# APU_PayloadBoard_Schematic.net
KiCad netlist of a schematic drawn in EAGLE
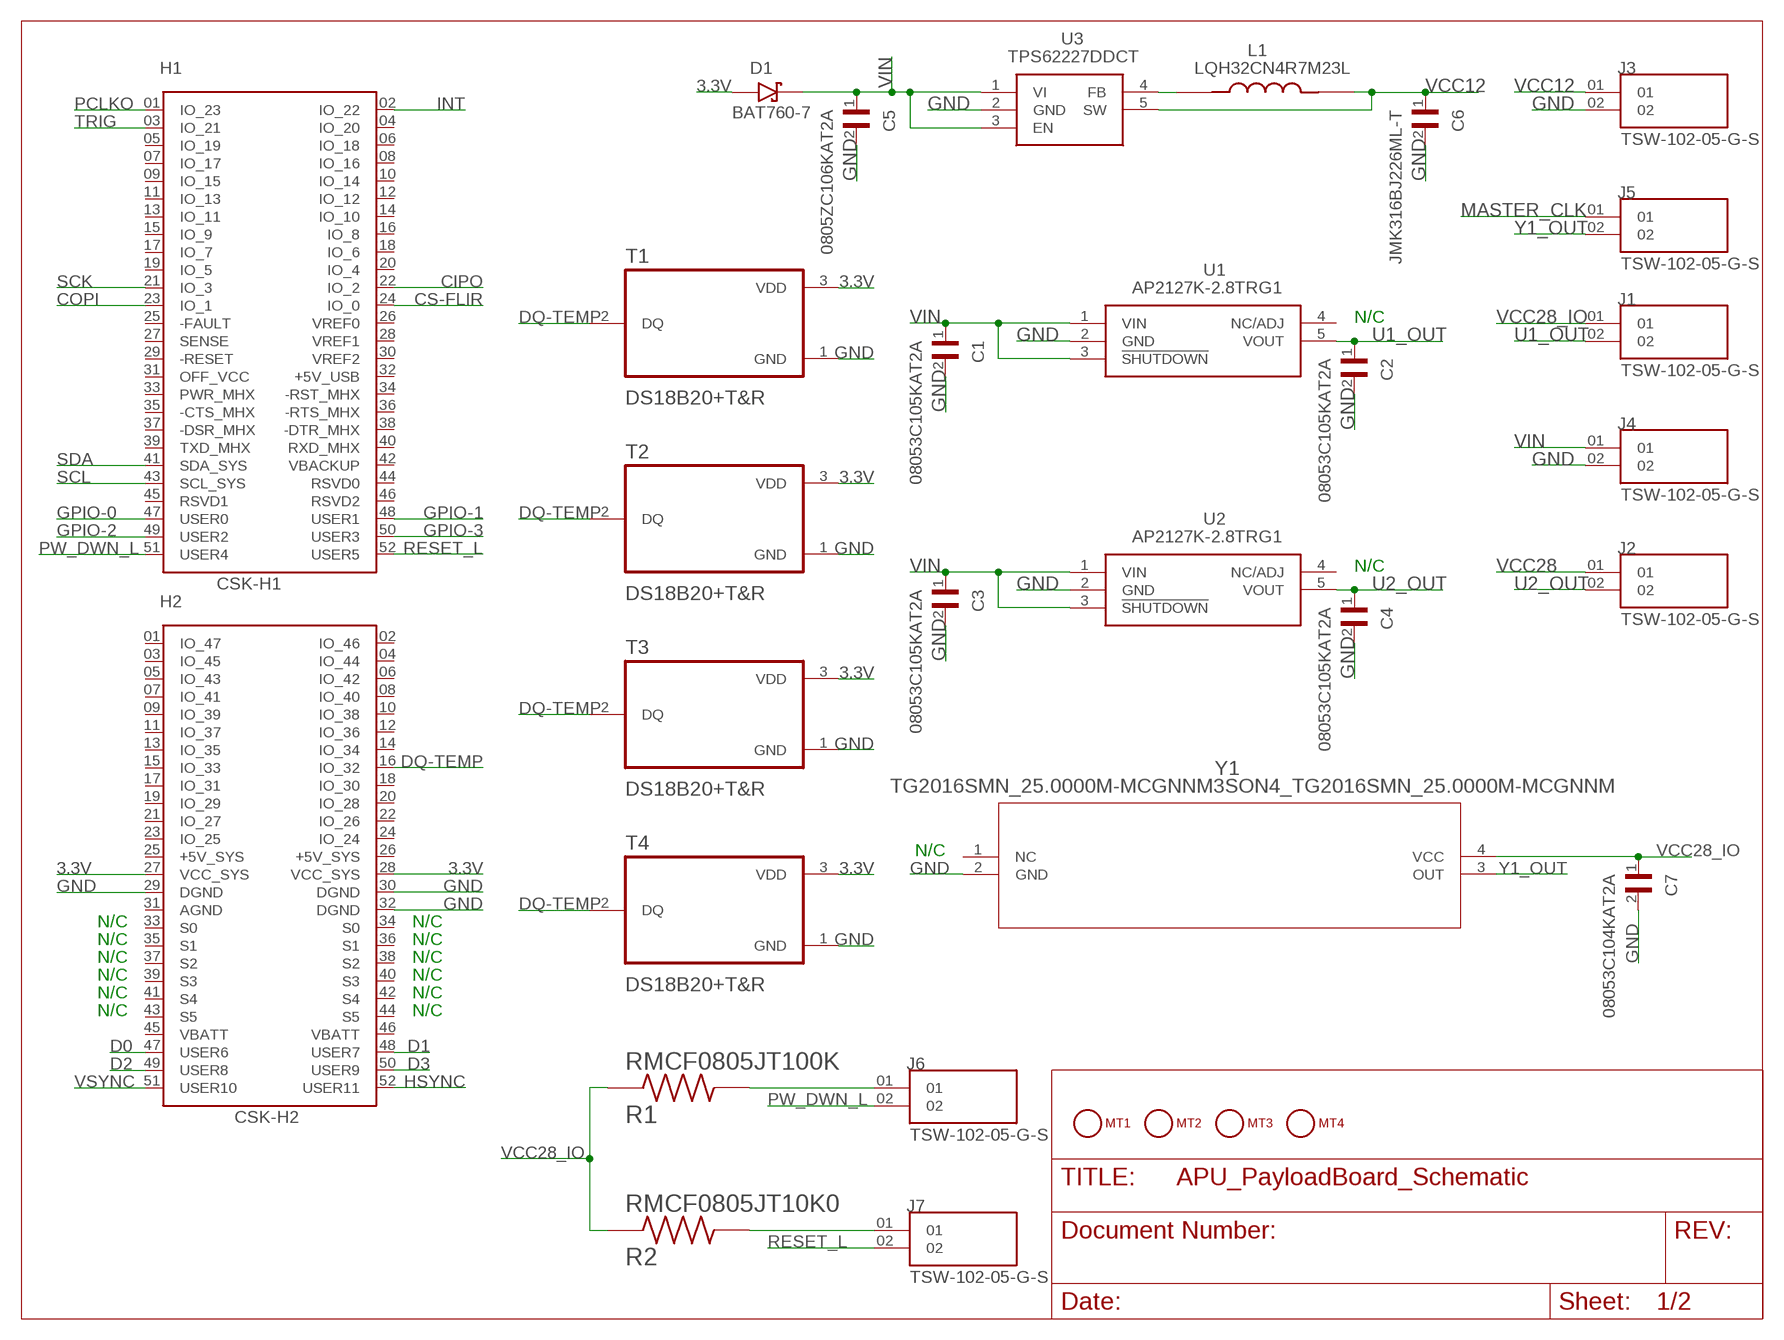
[diagram p0: schematic, sheet 1]
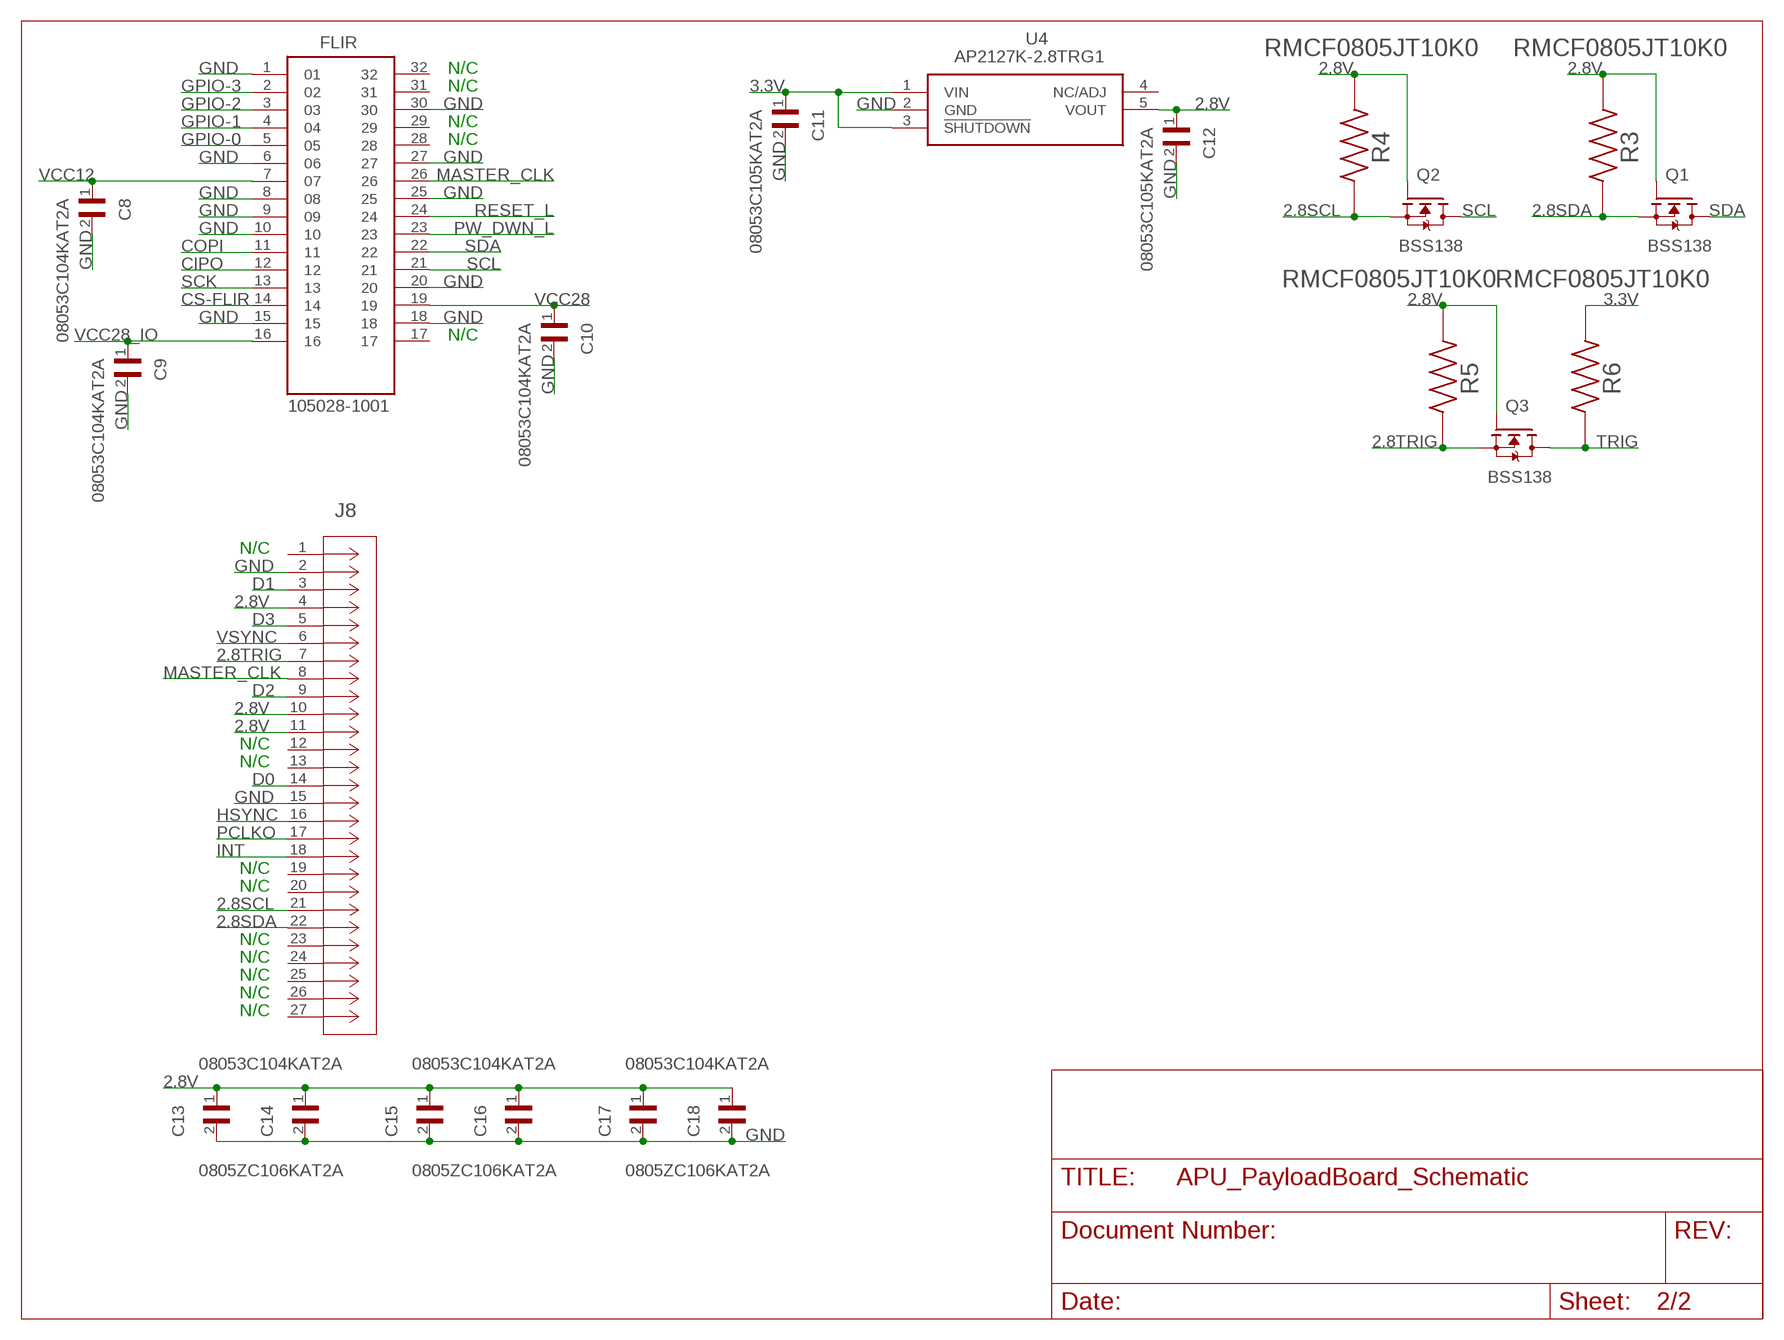
[diagram p1: schematic, sheet 2]

(export (version "E")
  (design (tool "Eeschema 10.0.6"))
  (components
    (comp (ref "C1")
      (value "08053C105KAT2A")
      (footprint "eagle-import:CAPC2012X94N")
      (fields (field (name "MF") "AVX"))
      (libsource (lib "eagle-import") (part "08053C105KAT2A"))
    )
    (comp (ref "C2")
      (value "08053C105KAT2A")
      (footprint "eagle-import:CAPC2012X94N")
      (fields (field (name "MF") "AVX"))
      (libsource (lib "eagle-import") (part "08053C105KAT2A"))
    )
    (comp (ref "C3")
      (value "08053C105KAT2A")
      (footprint "eagle-import:CAPC2012X94N")
      (fields (field (name "MF") "AVX"))
      (libsource (lib "eagle-import") (part "08053C105KAT2A"))
    )
    (comp (ref "C4")
      (value "08053C105KAT2A")
      (footprint "eagle-import:CAPC2012X94N")
      (fields (field (name "MF") "AVX"))
      (libsource (lib "eagle-import") (part "08053C105KAT2A"))
    )
    (comp (ref "C5")
      (value "0805ZC106KAT2A")
      (footprint "eagle-import:CAPC2012X152N")
      (fields (field (name "MF") "AVX"))
      (libsource (lib "eagle-import") (part "0805ZC106KAT2A"))
    )
    (comp (ref "C6")
      (value "JMK316BJ226ML-T")
      (footprint "eagle-import:CAPC3216X180N")
      (fields (field (name "MF") "Taiyo Yuden"))
      (libsource (lib "eagle-import") (part "JMK316BJ226ML-T"))
    )
    (comp (ref "C7")
      (value "08053C104KAT2A")
      (footprint "eagle-import:CAPC2012X94N")
      (fields (field (name "MF") "AVX"))
      (libsource (lib "eagle-import") (part "08053C104KAT2A"))
    )
    (comp (ref "D1")
      (value "BAT760-7")
      (footprint "eagle-import:SOD2513X120N")
      (fields (field (name "MF") "Diodes Inc."))
      (libsource (lib "eagle-import") (part "BAT760-7"))
    )
    (comp (ref "H1")
      (value "CSK-H1")
      (footprint "eagle-import:SAMTEC_ESQ-126-37-G-D--NUMBERED-FOR-CUBESAT-BUS")
      (libsource (lib "eagle-import") (part "CSK-H1"))
    )
    (comp (ref "H2")
      (value "CSK-H2")
      (footprint "eagle-import:SAMTEC_ESQ-126-37-G-D--NUMBERED-FOR-CUBESAT-BUS")
      (libsource (lib "eagle-import") (part "CSK-H2"))
    )
    (comp (ref "J1")
      (value "TSW-102-05-G-S")
      (footprint "eagle-import:SAMTEC_TSW-102-05-G-S")
      (fields (field (name "MF") "Samtec Inc."))
      (libsource (lib "eagle-import") (part "TSW-102-05-G-S"))
    )
    (comp (ref "J2")
      (value "TSW-102-05-G-S")
      (footprint "eagle-import:SAMTEC_TSW-102-05-G-S")
      (fields (field (name "MF") "Samtec Inc."))
      (libsource (lib "eagle-import") (part "TSW-102-05-G-S"))
    )
    (comp (ref "J3")
      (value "TSW-102-05-G-S")
      (footprint "eagle-import:SAMTEC_TSW-102-05-G-S")
      (fields (field (name "MF") "Samtec Inc."))
      (libsource (lib "eagle-import") (part "TSW-102-05-G-S"))
    )
    (comp (ref "J4")
      (value "TSW-102-05-G-S")
      (footprint "eagle-import:SAMTEC_TSW-102-05-G-S")
      (fields (field (name "MF") "Samtec Inc."))
      (libsource (lib "eagle-import") (part "TSW-102-05-G-S"))
    )
    (comp (ref "J5")
      (value "TSW-102-05-G-S")
      (footprint "eagle-import:SAMTEC_TSW-102-05-G-S")
      (fields (field (name "MF") "Samtec Inc."))
      (libsource (lib "eagle-import") (part "TSW-102-05-G-S"))
    )
    (comp (ref "J6")
      (value "TSW-102-05-G-S")
      (footprint "eagle-import:SAMTEC_TSW-102-05-G-S")
      (fields (field (name "MF") "Samtec Inc."))
      (libsource (lib "eagle-import") (part "TSW-102-05-G-S"))
    )
    (comp (ref "J7")
      (value "TSW-102-05-G-S")
      (footprint "eagle-import:SAMTEC_TSW-102-05-G-S")
      (fields (field (name "MF") "Samtec Inc."))
      (libsource (lib "eagle-import") (part "TSW-102-05-G-S"))
    )
    (comp (ref "L1")
      (value "LQH32CN4R7M23L")
      (footprint "eagle-import:IND_LQH32CN4R7M23L")
      (fields (field (name "MF") "Murata Electronics"))
      (libsource (lib "eagle-import") (part "LQH32CN4R7M23L"))
    )
    (comp (ref "MT1")
      (value "MOUNTING_HOLE-125_250_ROUND")
      (footprint "eagle-import:MT_125_250")
      (libsource (lib "eagle-import") (part "MOUNTING_HOLE-125_250_ROUND"))
    )
    (comp (ref "MT2")
      (value "MOUNTING_HOLE-125_250_ROUND")
      (footprint "eagle-import:MT_125_250")
      (libsource (lib "eagle-import") (part "MOUNTING_HOLE-125_250_ROUND"))
    )
    (comp (ref "MT3")
      (value "MOUNTING_HOLE-125_250_ROUND")
      (footprint "eagle-import:MT_125_250")
      (libsource (lib "eagle-import") (part "MOUNTING_HOLE-125_250_ROUND"))
    )
    (comp (ref "MT4")
      (value "MOUNTING_HOLE-125_250_ROUND")
      (footprint "eagle-import:MT_125_250")
      (libsource (lib "eagle-import") (part "MOUNTING_HOLE-125_250_ROUND"))
    )
    (comp (ref "R1")
      (value "RMCF0805JT100K")
      (footprint "eagle-import:RESC2012X65N")
      (fields (field (name "MF") "Stackpole Electronics Inc"))
      (libsource (lib "eagle-import") (part "RMCF0805JT100K"))
    )
    (comp (ref "R2")
      (value "RMCF0805JT10K0")
      (footprint "eagle-import:RESC2012X65N")
      (fields (field (name "MF") "Stackpole Electronics Inc"))
      (libsource (lib "eagle-import") (part "RMCF0805JT10K0"))
    )
    (comp (ref "T1")
      (value "DS18B20+T&R")
      (footprint "eagle-import:DS18B20+T&R")
      (libsource (lib "eagle-import") (part "DS18B20+T&R"))
    )
    (comp (ref "T2")
      (value "DS18B20+T&R")
      (footprint "eagle-import:DS18B20+T&R")
      (libsource (lib "eagle-import") (part "DS18B20+T&R"))
    )
    (comp (ref "T3")
      (value "DS18B20+T&R")
      (footprint "eagle-import:DS18B20+T&R")
      (libsource (lib "eagle-import") (part "DS18B20+T&R"))
    )
    (comp (ref "T4")
      (value "DS18B20+T&R")
      (footprint "eagle-import:DS18B20+T&R")
      (libsource (lib "eagle-import") (part "DS18B20+T&R"))
    )
    (comp (ref "U1")
      (value "AP2127K-2.8TRG1")
      (footprint "eagle-import:SOT95P282X145-5N")
      (fields (field (name "MOUSER_PART_NUMBER") "621-AP2127K-2.8TRG1"))
      (libsource (lib "eagle-import") (part "AP2127K-2.8TRG1"))
    )
    (comp (ref "U2")
      (value "AP2127K-2.8TRG1")
      (footprint "eagle-import:SOT95P282X145-5N")
      (fields (field (name "MOUSER_PART_NUMBER") "621-AP2127K-2.8TRG1"))
      (libsource (lib "eagle-import") (part "AP2127K-2.8TRG1"))
    )
    (comp (ref "U3")
      (value "TPS62227DDCT")
      (footprint "eagle-import:SOT95P280X110-5N")
      (fields (field (name "MOUSER_PART_NUMBER") "595-TPS62227DDCT"))
      (libsource (lib "eagle-import") (part "TPS62227DDCT"))
    )
    (comp (ref "Y1")
      (value "TG2016SMN_25.0000M-MCGNNM3SON4_TG2016SMN_25.0000M-MCGNNM")
      (footprint "eagle-import:SON4_TG2016SMN_25.0000M-MCGNNM")
      (fields
        (field (name "MANUFACTURER_PART_NUMBER") "TG2016SMN 25.0000M-MCGNNM3")
        (field (name "COPYRIGHT") "Copyright (C) 2023 Ultra Librarian. All rights reserved.")
      )
      (libsource (lib "eagle-import") (part "TG2016SMN_25.0000M-MCGNNM3SON4_TG2016SMN_25.0000M-MCGNNM"))
    )
    (comp (ref "C8")
      (value "08053C104KAT2A")
      (footprint "eagle-import:CAPC2012X94N")
      (fields (field (name "MF") "AVX"))
      (libsource (lib "eagle-import") (part "08053C104KAT2A"))
    )
    (comp (ref "C9")
      (value "08053C104KAT2A")
      (footprint "eagle-import:CAPC2012X94N")
      (fields (field (name "MF") "AVX"))
      (libsource (lib "eagle-import") (part "08053C104KAT2A"))
    )
    (comp (ref "C10")
      (value "08053C104KAT2A")
      (footprint "eagle-import:CAPC2012X94N")
      (fields (field (name "MF") "AVX"))
      (libsource (lib "eagle-import") (part "08053C104KAT2A"))
    )
    (comp (ref "C11")
      (value "08053C105KAT2A")
      (footprint "eagle-import:CAPC2012X94N")
      (fields (field (name "MF") "AVX"))
      (libsource (lib "eagle-import") (part "08053C105KAT2A"))
    )
    (comp (ref "C12")
      (value "08053C105KAT2A")
      (footprint "eagle-import:CAPC2012X94N")
      (fields (field (name "MF") "AVX"))
      (libsource (lib "eagle-import") (part "08053C105KAT2A"))
    )
    (comp (ref "C13")
      (value "08053C104KAT2A")
      (footprint "eagle-import:CAPC2012X94N")
      (fields (field (name "MF") "AVX"))
      (libsource (lib "eagle-import") (part "08053C104KAT2A"))
    )
    (comp (ref "C14")
      (value "0805ZC106KAT2A")
      (footprint "eagle-import:CAPC2012X152N")
      (fields (field (name "MF") "AVX"))
      (libsource (lib "eagle-import") (part "0805ZC106KAT2A"))
    )
    (comp (ref "C15")
      (value "08053C104KAT2A")
      (footprint "eagle-import:CAPC2012X94N")
      (fields (field (name "MF") "AVX"))
      (libsource (lib "eagle-import") (part "08053C104KAT2A"))
    )
    (comp (ref "C16")
      (value "0805ZC106KAT2A")
      (footprint "eagle-import:CAPC2012X152N")
      (fields (field (name "MF") "AVX"))
      (libsource (lib "eagle-import") (part "0805ZC106KAT2A"))
    )
    (comp (ref "C17")
      (value "08053C104KAT2A")
      (footprint "eagle-import:CAPC2012X94N")
      (fields (field (name "MF") "AVX"))
      (libsource (lib "eagle-import") (part "08053C104KAT2A"))
    )
    (comp (ref "C18")
      (value "0805ZC106KAT2A")
      (footprint "eagle-import:CAPC2012X152N")
      (fields (field (name "MF") "AVX"))
      (libsource (lib "eagle-import") (part "0805ZC106KAT2A"))
    )
    (comp (ref "FLIR")
      (value "105028-1001")
      (footprint "eagle-import:MOLEX_105028-1001")
      (fields (field (name "MF") "Molex") (field (name "MP") "1050281001"))
      (libsource (lib "eagle-import") (part "105028-1001"))
    )
    (comp (ref "J8")
      (value "SFV25R-1STE1LFCON25_1X25_DR_SFV_JAE")
      (footprint "eagle-import:CON25_1X25_DR_SFV_JAE")
      (fields
        (field (name "MANUFACTURER_PART_NUMBER") "SFV25R-1STE1LF")
        (field (name "COPYRIGHT") "Copyright (C) 2023 Ultra Librarian. All rights reserved.")
      )
      (libsource (lib "eagle-import") (part "SFV25R-1STE1LFCON25_1X25_DR_SFV_JAE"))
    )
    (comp (ref "Q1")
      (value "BSS138")
      (footprint "eagle-import:SOT95P240X111-3N")
      (fields (field (name "MF") "onsemi"))
      (libsource (lib "eagle-import") (part "BSS138"))
    )
    (comp (ref "Q2")
      (value "BSS138")
      (footprint "eagle-import:SOT95P240X111-3N")
      (fields (field (name "MF") "onsemi"))
      (libsource (lib "eagle-import") (part "BSS138"))
    )
    (comp (ref "Q3")
      (value "BSS138")
      (footprint "eagle-import:SOT95P240X111-3N")
      (fields (field (name "MF") "onsemi"))
      (libsource (lib "eagle-import") (part "BSS138"))
    )
    (comp (ref "R3")
      (value "RMCF0805JT10K0")
      (footprint "eagle-import:RESC2012X65N")
      (fields (field (name "MF") "Stackpole Electronics Inc"))
      (libsource (lib "eagle-import") (part "RMCF0805JT10K0"))
    )
    (comp (ref "R4")
      (value "RMCF0805JT10K0")
      (footprint "eagle-import:RESC2012X65N")
      (fields (field (name "MF") "Stackpole Electronics Inc"))
      (libsource (lib "eagle-import") (part "RMCF0805JT10K0"))
    )
    (comp (ref "R5")
      (value "RMCF0805JT10K0")
      (footprint "eagle-import:RESC2012X65N")
      (fields (field (name "MF") "Stackpole Electronics Inc"))
      (libsource (lib "eagle-import") (part "RMCF0805JT10K0"))
    )
    (comp (ref "R6")
      (value "RMCF0805JT10K0")
      (footprint "eagle-import:RESC2012X65N")
      (fields (field (name "MF") "Stackpole Electronics Inc"))
      (libsource (lib "eagle-import") (part "RMCF0805JT10K0"))
    )
    (comp (ref "U4")
      (value "AP2127K-2.8TRG1")
      (footprint "eagle-import:SOT95P282X145-5N")
      (fields (field (name "MOUSER_PART_NUMBER") "621-AP2127K-2.8TRG1"))
      (libsource (lib "eagle-import") (part "AP2127K-2.8TRG1"))
    )
  )
  (nets
    (net (code "1") (name "2.8SCL") (class "Default")
      (node (ref "J8") (pin "21") (pinfunction "21_21") (pintype "passive"))
      (node (ref "Q2") (pin "2") (pinfunction "S_2") (pintype "passive"))
      (node (ref "R4") (pin "1") (pinfunction "1_1") (pintype "passive"))
    )
    (net (code "2") (name "2.8SDA") (class "Default")
      (node (ref "J8") (pin "22") (pinfunction "22_22") (pintype "passive"))
      (node (ref "Q1") (pin "2") (pinfunction "S_2") (pintype "passive"))
      (node (ref "R3") (pin "1") (pinfunction "1_1") (pintype "passive"))
    )
    (net (code "3") (name "2.8TRIG") (class "Default")
      (node (ref "J8") (pin "7") (pinfunction "7_7") (pintype "passive"))
      (node (ref "Q3") (pin "2") (pinfunction "S_2") (pintype "passive"))
      (node (ref "R5") (pin "1") (pinfunction "1_1") (pintype "passive"))
    )
    (net (code "4") (name "2.8V") (class "Default")
      (node (ref "C12") (pin "1") (pinfunction "1_1") (pintype "passive"))
      (node (ref "C13") (pin "1") (pinfunction "1_1") (pintype "passive"))
      (node (ref "C14") (pin "1") (pinfunction "1_1") (pintype "passive"))
      (node (ref "C15") (pin "1") (pinfunction "1_1") (pintype "passive"))
      (node (ref "C16") (pin "1") (pinfunction "1_1") (pintype "passive"))
      (node (ref "C17") (pin "1") (pinfunction "1_1") (pintype "passive"))
      (node (ref "C18") (pin "1") (pinfunction "1_1") (pintype "passive"))
      (node (ref "J8") (pin "10") (pinfunction "10_10") (pintype "passive"))
      (node (ref "J8") (pin "11") (pinfunction "11_11") (pintype "passive"))
      (node (ref "J8") (pin "4") (pinfunction "4_4") (pintype "passive"))
      (node (ref "Q1") (pin "1") (pinfunction "G_1") (pintype "passive"))
      (node (ref "Q2") (pin "1") (pinfunction "G_1") (pintype "passive"))
      (node (ref "Q3") (pin "1") (pinfunction "G_1") (pintype "passive"))
      (node (ref "R3") (pin "2") (pinfunction "2_2") (pintype "passive"))
      (node (ref "R4") (pin "2") (pinfunction "2_2") (pintype "passive"))
      (node (ref "R5") (pin "2") (pinfunction "2_2") (pintype "passive"))
      (node (ref "U4") (pin "5") (pinfunction "VOUT_5") (pintype "bidirectional"))
    )
    (net (code "5") (name "3.3V") (class "Default")
      (node (ref "C11") (pin "1") (pinfunction "1_1") (pintype "passive"))
      (node (ref "D1") (pin "A") (pinfunction "A_A") (pintype "passive"))
      (node (ref "H2") (pin "27") (pinfunction "VCC_SYS_27") (pintype "bidirectional"))
      (node (ref "H2") (pin "28") (pinfunction "VCC_SYS_28") (pintype "bidirectional"))
      (node (ref "R6") (pin "2") (pinfunction "2_2") (pintype "passive"))
      (node (ref "T1") (pin "3") (pinfunction "VDD_3") (pintype "bidirectional"))
      (node (ref "T2") (pin "3") (pinfunction "VDD_3") (pintype "bidirectional"))
      (node (ref "T3") (pin "3") (pinfunction "VDD_3") (pintype "bidirectional"))
      (node (ref "T4") (pin "3") (pinfunction "VDD_3") (pintype "bidirectional"))
      (node (ref "U4") (pin "1") (pinfunction "VIN_1") (pintype "bidirectional"))
      (node (ref "U4") (pin "3") (pinfunction "~{SHUTDOWN}_3") (pintype "bidirectional"))
    )
    (net (code "6") (name "CIPO") (class "Default")
      (node (ref "FLIR") (pin "12") (pinfunction "12_12") (pintype "passive"))
      (node (ref "H1") (pin "22") (pinfunction "IO_2_22") (pintype "bidirectional"))
    )
    (net (code "7") (name "COPI") (class "Default")
      (node (ref "FLIR") (pin "11") (pinfunction "11_11") (pintype "passive"))
      (node (ref "H1") (pin "23") (pinfunction "IO_1_23") (pintype "bidirectional"))
    )
    (net (code "8") (name "CS-FLIR") (class "Default")
      (node (ref "FLIR") (pin "14") (pinfunction "14_14") (pintype "passive"))
      (node (ref "H1") (pin "24") (pinfunction "IO_0_24") (pintype "bidirectional"))
    )
    (net (code "9") (name "D0") (class "Default")
      (node (ref "H2") (pin "47") (pinfunction "USER6_47") (pintype "bidirectional"))
      (node (ref "J8") (pin "14") (pinfunction "14_14") (pintype "passive"))
    )
    (net (code "10") (name "D1") (class "Default")
      (node (ref "H2") (pin "48") (pinfunction "USER7_48") (pintype "bidirectional"))
      (node (ref "J8") (pin "3") (pinfunction "3_3") (pintype "passive"))
    )
    (net (code "11") (name "D2") (class "Default")
      (node (ref "H2") (pin "49") (pinfunction "USER8_49") (pintype "bidirectional"))
      (node (ref "J8") (pin "9") (pinfunction "9_9") (pintype "passive"))
    )
    (net (code "12") (name "D3") (class "Default")
      (node (ref "H2") (pin "50") (pinfunction "USER9_50") (pintype "bidirectional"))
      (node (ref "J8") (pin "5") (pinfunction "5_5") (pintype "passive"))
    )
    (net (code "13") (name "DQ-TEMP") (class "Default")
      (node (ref "H2") (pin "16") (pinfunction "IO_32_16") (pintype "bidirectional"))
      (node (ref "T1") (pin "2") (pinfunction "DQ_2") (pintype "bidirectional"))
      (node (ref "T2") (pin "2") (pinfunction "DQ_2") (pintype "bidirectional"))
      (node (ref "T3") (pin "2") (pinfunction "DQ_2") (pintype "bidirectional"))
      (node (ref "T4") (pin "2") (pinfunction "DQ_2") (pintype "bidirectional"))
    )
    (net (code "14") (name "GND") (class "Default")
      (node (ref "C1") (pin "2") (pinfunction "2_2") (pintype "passive"))
      (node (ref "C10") (pin "2") (pinfunction "2_2") (pintype "passive"))
      (node (ref "C11") (pin "2") (pinfunction "2_2") (pintype "passive"))
      (node (ref "C12") (pin "2") (pinfunction "2_2") (pintype "passive"))
      (node (ref "C13") (pin "2") (pinfunction "2_2") (pintype "passive"))
      (node (ref "C14") (pin "2") (pinfunction "2_2") (pintype "passive"))
      (node (ref "C15") (pin "2") (pinfunction "2_2") (pintype "passive"))
      (node (ref "C16") (pin "2") (pinfunction "2_2") (pintype "passive"))
      (node (ref "C17") (pin "2") (pinfunction "2_2") (pintype "passive"))
      (node (ref "C18") (pin "2") (pinfunction "2_2") (pintype "passive"))
      (node (ref "C2") (pin "2") (pinfunction "2_2") (pintype "passive"))
      (node (ref "C3") (pin "2") (pinfunction "2_2") (pintype "passive"))
      (node (ref "C4") (pin "2") (pinfunction "2_2") (pintype "passive"))
      (node (ref "C5") (pin "2") (pinfunction "2_2") (pintype "passive"))
      (node (ref "C6") (pin "2") (pinfunction "2_2") (pintype "passive"))
      (node (ref "C7") (pin "2") (pinfunction "2_2") (pintype "passive"))
      (node (ref "C8") (pin "2") (pinfunction "2_2") (pintype "passive"))
      (node (ref "C9") (pin "2") (pinfunction "2_2") (pintype "passive"))
      (node (ref "FLIR") (pin "1") (pinfunction "01_1") (pintype "passive"))
      (node (ref "FLIR") (pin "10") (pinfunction "10_10") (pintype "passive"))
      (node (ref "FLIR") (pin "15") (pinfunction "15_15") (pintype "passive"))
      (node (ref "FLIR") (pin "18") (pinfunction "18_18") (pintype "passive"))
      (node (ref "FLIR") (pin "20") (pinfunction "20_20") (pintype "passive"))
      (node (ref "FLIR") (pin "25") (pinfunction "25_25") (pintype "passive"))
      (node (ref "FLIR") (pin "27") (pinfunction "27_27") (pintype "passive"))
      (node (ref "FLIR") (pin "30") (pinfunction "30_30") (pintype "passive"))
      (node (ref "FLIR") (pin "6") (pinfunction "06_6") (pintype "passive"))
      (node (ref "FLIR") (pin "8") (pinfunction "08_8") (pintype "passive"))
      (node (ref "FLIR") (pin "9") (pinfunction "09_9") (pintype "passive"))
      (node (ref "H2") (pin "29") (pinfunction "DGND_29") (pintype "bidirectional"))
      (node (ref "H2") (pin "30") (pinfunction "DGND_30") (pintype "bidirectional"))
      (node (ref "H2") (pin "32") (pinfunction "DGND_32") (pintype "bidirectional"))
      (node (ref "J3") (pin "02") (pinfunction "02_02") (pintype "passive"))
      (node (ref "J4") (pin "02") (pinfunction "02_02") (pintype "passive"))
      (node (ref "J8") (pin "15") (pinfunction "15_15") (pintype "passive"))
      (node (ref "J8") (pin "2") (pinfunction "2_2") (pintype "passive"))
      (node (ref "T1") (pin "1") (pinfunction "GND_1") (pintype "bidirectional"))
      (node (ref "T2") (pin "1") (pinfunction "GND_1") (pintype "bidirectional"))
      (node (ref "T3") (pin "1") (pinfunction "GND_1") (pintype "bidirectional"))
      (node (ref "T4") (pin "1") (pinfunction "GND_1") (pintype "bidirectional"))
      (node (ref "U1") (pin "2") (pinfunction "GND_2") (pintype "bidirectional"))
      (node (ref "U2") (pin "2") (pinfunction "GND_2") (pintype "bidirectional"))
      (node (ref "U3") (pin "2") (pinfunction "GND_2") (pintype "bidirectional"))
      (node (ref "U4") (pin "2") (pinfunction "GND_2") (pintype "bidirectional"))
      (node (ref "Y1") (pin "2") (pinfunction "GND_2") (pintype "passive"))
    )
    (net (code "15") (name "GPIO-0") (class "Default")
      (node (ref "FLIR") (pin "5") (pinfunction "05_5") (pintype "passive"))
      (node (ref "H1") (pin "47") (pinfunction "USER0_47") (pintype "bidirectional"))
    )
    (net (code "16") (name "GPIO-1") (class "Default")
      (node (ref "FLIR") (pin "4") (pinfunction "04_4") (pintype "passive"))
      (node (ref "H1") (pin "48") (pinfunction "USER1_48") (pintype "bidirectional"))
    )
    (net (code "17") (name "GPIO-2") (class "Default")
      (node (ref "FLIR") (pin "3") (pinfunction "03_3") (pintype "passive"))
      (node (ref "H1") (pin "49") (pinfunction "USER2_49") (pintype "bidirectional"))
    )
    (net (code "18") (name "GPIO-3") (class "Default")
      (node (ref "FLIR") (pin "2") (pinfunction "02_2") (pintype "passive"))
      (node (ref "H1") (pin "50") (pinfunction "USER3_50") (pintype "bidirectional"))
    )
    (net (code "19") (name "HSYNC") (class "Default")
      (node (ref "H2") (pin "52") (pinfunction "USER11_52") (pintype "bidirectional"))
      (node (ref "J8") (pin "16") (pinfunction "16_16") (pintype "passive"))
    )
    (net (code "20") (name "INT") (class "Default")
      (node (ref "H1") (pin "02") (pinfunction "IO_22_02") (pintype "bidirectional"))
      (node (ref "J8") (pin "18") (pinfunction "18_18") (pintype "passive"))
    )
    (net (code "21") (name "MASTER_CLK") (class "Default")
      (node (ref "FLIR") (pin "26") (pinfunction "26_26") (pintype "passive"))
      (node (ref "J5") (pin "01") (pinfunction "01_01") (pintype "passive"))
      (node (ref "J8") (pin "8") (pinfunction "8_8") (pintype "passive"))
    )
    (net (code "22") (name "Net-(J6-Pad01)") (class "Default")
      (node (ref "J6") (pin "01") (pinfunction "01_01") (pintype "passive"))
      (node (ref "R1") (pin "2") (pinfunction "2_2") (pintype "passive"))
    )
    (net (code "23") (name "Net-(J7-Pad01)") (class "Default")
      (node (ref "J7") (pin "01") (pinfunction "01_01") (pintype "passive"))
      (node (ref "R2") (pin "2") (pinfunction "2_2") (pintype "passive"))
    )
    (net (code "24") (name "Net-(U3-FB)") (class "Default")
      (node (ref "L1") (pin "1") (pinfunction "1_1") (pintype "passive"))
      (node (ref "U3") (pin "4") (pinfunction "FB_4") (pintype "bidirectional"))
    )
    (net (code "25") (name "PCLKO") (class "Default")
      (node (ref "H1") (pin "01") (pinfunction "IO_23_01") (pintype "bidirectional"))
      (node (ref "J8") (pin "17") (pinfunction "17_17") (pintype "passive"))
    )
    (net (code "26") (name "PW_DWN_L") (class "Default")
      (node (ref "FLIR") (pin "23") (pinfunction "23_23") (pintype "passive"))
      (node (ref "H1") (pin "51") (pinfunction "USER4_51") (pintype "bidirectional"))
      (node (ref "J6") (pin "02") (pinfunction "02_02") (pintype "passive"))
    )
    (net (code "27") (name "RESET_L") (class "Default")
      (node (ref "FLIR") (pin "24") (pinfunction "24_24") (pintype "passive"))
      (node (ref "H1") (pin "52") (pinfunction "USER5_52") (pintype "bidirectional"))
      (node (ref "J7") (pin "02") (pinfunction "02_02") (pintype "passive"))
    )
    (net (code "28") (name "SCK") (class "Default")
      (node (ref "FLIR") (pin "13") (pinfunction "13_13") (pintype "passive"))
      (node (ref "H1") (pin "21") (pinfunction "IO_3_21") (pintype "bidirectional"))
    )
    (net (code "29") (name "SCL") (class "Default")
      (node (ref "FLIR") (pin "21") (pinfunction "21_21") (pintype "passive"))
      (node (ref "H1") (pin "43") (pinfunction "SCL_SYS_43") (pintype "bidirectional"))
      (node (ref "Q2") (pin "3") (pinfunction "D_3") (pintype "passive"))
    )
    (net (code "30") (name "SDA") (class "Default")
      (node (ref "FLIR") (pin "22") (pinfunction "22_22") (pintype "passive"))
      (node (ref "H1") (pin "41") (pinfunction "SDA_SYS_41") (pintype "bidirectional"))
      (node (ref "Q1") (pin "3") (pinfunction "D_3") (pintype "passive"))
    )
    (net (code "31") (name "TRIG") (class "Default")
      (node (ref "H1") (pin "03") (pinfunction "IO_21_03") (pintype "bidirectional"))
      (node (ref "Q3") (pin "3") (pinfunction "D_3") (pintype "passive"))
      (node (ref "R6") (pin "1") (pinfunction "1_1") (pintype "passive"))
    )
    (net (code "32") (name "U1_OUT") (class "Default")
      (node (ref "C2") (pin "1") (pinfunction "1_1") (pintype "passive"))
      (node (ref "J1") (pin "02") (pinfunction "02_02") (pintype "passive"))
      (node (ref "U1") (pin "5") (pinfunction "VOUT_5") (pintype "bidirectional"))
    )
    (net (code "33") (name "U2_OUT") (class "Default")
      (node (ref "C4") (pin "1") (pinfunction "1_1") (pintype "passive"))
      (node (ref "J2") (pin "02") (pinfunction "02_02") (pintype "passive"))
      (node (ref "U2") (pin "5") (pinfunction "VOUT_5") (pintype "bidirectional"))
    )
    (net (code "34") (name "VCC12") (class "Default")
      (node (ref "C6") (pin "1") (pinfunction "1_1") (pintype "passive"))
      (node (ref "C8") (pin "1") (pinfunction "1_1") (pintype "passive"))
      (node (ref "FLIR") (pin "7") (pinfunction "07_7") (pintype "passive"))
      (node (ref "J3") (pin "01") (pinfunction "01_01") (pintype "passive"))
      (node (ref "L1") (pin "2") (pinfunction "2_2") (pintype "passive"))
      (node (ref "U3") (pin "5") (pinfunction "SW_5") (pintype "bidirectional"))
    )
    (net (code "35") (name "VCC28") (class "Default")
      (node (ref "C10") (pin "1") (pinfunction "1_1") (pintype "passive"))
      (node (ref "FLIR") (pin "19") (pinfunction "19_19") (pintype "passive"))
      (node (ref "J2") (pin "01") (pinfunction "01_01") (pintype "passive"))
    )
    (net (code "36") (name "VCC28_IO") (class "Default")
      (node (ref "C7") (pin "1") (pinfunction "1_1") (pintype "passive"))
      (node (ref "C9") (pin "1") (pinfunction "1_1") (pintype "passive"))
      (node (ref "FLIR") (pin "16") (pinfunction "16_16") (pintype "passive"))
      (node (ref "J1") (pin "01") (pinfunction "01_01") (pintype "passive"))
      (node (ref "R1") (pin "1") (pinfunction "1_1") (pintype "passive"))
      (node (ref "R2") (pin "1") (pinfunction "1_1") (pintype "passive"))
      (node (ref "Y1") (pin "4") (pinfunction "VCC_4") (pintype "power_in"))
    )
    (net (code "37") (name "VIN") (class "Default")
      (node (ref "C1") (pin "1") (pinfunction "1_1") (pintype "passive"))
      (node (ref "C3") (pin "1") (pinfunction "1_1") (pintype "passive"))
      (node (ref "C5") (pin "1") (pinfunction "1_1") (pintype "passive"))
      (node (ref "D1") (pin "C") (pinfunction "K_C") (pintype "passive"))
      (node (ref "J4") (pin "01") (pinfunction "01_01") (pintype "passive"))
      (node (ref "U1") (pin "1") (pinfunction "VIN_1") (pintype "bidirectional"))
      (node (ref "U1") (pin "3") (pinfunction "~{SHUTDOWN}_3") (pintype "bidirectional"))
      (node (ref "U2") (pin "1") (pinfunction "VIN_1") (pintype "bidirectional"))
      (node (ref "U2") (pin "3") (pinfunction "~{SHUTDOWN}_3") (pintype "bidirectional"))
      (node (ref "U3") (pin "1") (pinfunction "VI_1") (pintype "bidirectional"))
      (node (ref "U3") (pin "3") (pinfunction "EN_3") (pintype "bidirectional"))
    )
    (net (code "38") (name "VSYNC") (class "Default")
      (node (ref "H2") (pin "51") (pinfunction "USER10_51") (pintype "bidirectional"))
      (node (ref "J8") (pin "6") (pinfunction "6_6") (pintype "passive"))
    )
    (net (code "39") (name "Y1_OUT") (class "Default")
      (node (ref "J5") (pin "02") (pinfunction "02_02") (pintype "passive"))
      (node (ref "Y1") (pin "3") (pinfunction "OUT_3") (pintype "output"))
    )
    (net (code "40") (name "unconnected-(FLIR-Pad17)") (class "Default")
      (node (ref "FLIR") (pin "17") (pinfunction "17_17") (pintype "passive"))
    )
    (net (code "41") (name "unconnected-(FLIR-Pad28)") (class "Default")
      (node (ref "FLIR") (pin "28") (pinfunction "28_28") (pintype "passive"))
    )
    (net (code "42") (name "unconnected-(FLIR-Pad29)") (class "Default")
      (node (ref "FLIR") (pin "29") (pinfunction "29_29") (pintype "passive"))
    )
    (net (code "43") (name "unconnected-(FLIR-Pad31)") (class "Default")
      (node (ref "FLIR") (pin "31") (pinfunction "31_31") (pintype "passive"))
    )
    (net (code "44") (name "unconnected-(FLIR-Pad32)") (class "Default")
      (node (ref "FLIR") (pin "32") (pinfunction "32_32") (pintype "passive"))
    )
    (net (code "45") (name "unconnected-(H1-+5V_USB-Pad32)") (class "Default")
      (node (ref "H1") (pin "32") (pinfunction "+5V_USB_32") (pintype "bidirectional"))
    )
    (net (code "46") (name "unconnected-(H1--CTS_MHX-Pad35)") (class "Default")
      (node (ref "H1") (pin "35") (pinfunction "-CTS_MHX_35") (pintype "bidirectional"))
    )
    (net (code "47") (name "unconnected-(H1--DSR_MHX-Pad37)") (class "Default")
      (node (ref "H1") (pin "37") (pinfunction "-DSR_MHX_37") (pintype "bidirectional"))
    )
    (net (code "48") (name "unconnected-(H1--DTR_MHX-Pad38)") (class "Default")
      (node (ref "H1") (pin "38") (pinfunction "-DTR_MHX_38") (pintype "bidirectional"))
    )
    (net (code "49") (name "unconnected-(H1--FAULT-Pad25)") (class "Default")
      (node (ref "H1") (pin "25") (pinfunction "-FAULT_25") (pintype "bidirectional"))
    )
    (net (code "50") (name "unconnected-(H1--RESET-Pad29)") (class "Default")
      (node (ref "H1") (pin "29") (pinfunction "-RESET_29") (pintype "bidirectional"))
    )
    (net (code "51") (name "unconnected-(H1--RST_MHX-Pad34)") (class "Default")
      (node (ref "H1") (pin "34") (pinfunction "-RST_MHX_34") (pintype "bidirectional"))
    )
    (net (code "52") (name "unconnected-(H1--RTS_MHX-Pad36)") (class "Default")
      (node (ref "H1") (pin "36") (pinfunction "-RTS_MHX_36") (pintype "bidirectional"))
    )
    (net (code "53") (name "unconnected-(H1-IO_4-Pad20)") (class "Default")
      (node (ref "H1") (pin "20") (pinfunction "IO_4_20") (pintype "bidirectional"))
    )
    (net (code "54") (name "unconnected-(H1-IO_5-Pad19)") (class "Default")
      (node (ref "H1") (pin "19") (pinfunction "IO_5_19") (pintype "bidirectional"))
    )
    (net (code "55") (name "unconnected-(H1-IO_6-Pad18)") (class "Default")
      (node (ref "H1") (pin "18") (pinfunction "IO_6_18") (pintype "bidirectional"))
    )
    (net (code "56") (name "unconnected-(H1-IO_7-Pad17)") (class "Default")
      (node (ref "H1") (pin "17") (pinfunction "IO_7_17") (pintype "bidirectional"))
    )
    (net (code "57") (name "unconnected-(H1-IO_8-Pad16)") (class "Default")
      (node (ref "H1") (pin "16") (pinfunction "IO_8_16") (pintype "bidirectional"))
    )
    (net (code "58") (name "unconnected-(H1-IO_9-Pad15)") (class "Default")
      (node (ref "H1") (pin "15") (pinfunction "IO_9_15") (pintype "bidirectional"))
    )
    (net (code "59") (name "unconnected-(H1-IO_10-Pad14)") (class "Default")
      (node (ref "H1") (pin "14") (pinfunction "IO_10_14") (pintype "bidirectional"))
    )
    (net (code "60") (name "unconnected-(H1-IO_11-Pad13)") (class "Default")
      (node (ref "H1") (pin "13") (pinfunction "IO_11_13") (pintype "bidirectional"))
    )
    (net (code "61") (name "unconnected-(H1-IO_12-Pad12)") (class "Default")
      (node (ref "H1") (pin "12") (pinfunction "IO_12_12") (pintype "bidirectional"))
    )
    (net (code "62") (name "unconnected-(H1-IO_13-Pad11)") (class "Default")
      (node (ref "H1") (pin "11") (pinfunction "IO_13_11") (pintype "bidirectional"))
    )
    (net (code "63") (name "unconnected-(H1-IO_14-Pad10)") (class "Default")
      (node (ref "H1") (pin "10") (pinfunction "IO_14_10") (pintype "bidirectional"))
    )
    (net (code "64") (name "unconnected-(H1-IO_15-Pad09)") (class "Default")
      (node (ref "H1") (pin "09") (pinfunction "IO_15_09") (pintype "bidirectional"))
    )
    (net (code "65") (name "unconnected-(H1-IO_16-Pad08)") (class "Default")
      (node (ref "H1") (pin "08") (pinfunction "IO_16_08") (pintype "bidirectional"))
    )
    (net (code "66") (name "unconnected-(H1-IO_17-Pad07)") (class "Default")
      (node (ref "H1") (pin "07") (pinfunction "IO_17_07") (pintype "bidirectional"))
    )
    (net (code "67") (name "unconnected-(H1-IO_18-Pad06)") (class "Default")
      (node (ref "H1") (pin "06") (pinfunction "IO_18_06") (pintype "bidirectional"))
    )
    (net (code "68") (name "unconnected-(H1-IO_19-Pad05)") (class "Default")
      (node (ref "H1") (pin "05") (pinfunction "IO_19_05") (pintype "bidirectional"))
    )
    (net (code "69") (name "unconnected-(H1-IO_20-Pad04)") (class "Default")
      (node (ref "H1") (pin "04") (pinfunction "IO_20_04") (pintype "bidirectional"))
    )
    (net (code "70") (name "unconnected-(H1-OFF_VCC-Pad31)") (class "Default")
      (node (ref "H1") (pin "31") (pinfunction "OFF_VCC_31") (pintype "bidirectional"))
    )
    (net (code "71") (name "unconnected-(H1-PWR_MHX-Pad33)") (class "Default")
      (node (ref "H1") (pin "33") (pinfunction "PWR_MHX_33") (pintype "bidirectional"))
    )
    (net (code "72") (name "unconnected-(H1-RSVD0-Pad44)") (class "Default")
      (node (ref "H1") (pin "44") (pinfunction "RSVD0_44") (pintype "bidirectional"))
    )
    (net (code "73") (name "unconnected-(H1-RSVD1-Pad45)") (class "Default")
      (node (ref "H1") (pin "45") (pinfunction "RSVD1_45") (pintype "bidirectional"))
    )
    (net (code "74") (name "unconnected-(H1-RSVD2-Pad46)") (class "Default")
      (node (ref "H1") (pin "46") (pinfunction "RSVD2_46") (pintype "bidirectional"))
    )
    (net (code "75") (name "unconnected-(H1-RXD_MHX-Pad40)") (class "Default")
      (node (ref "H1") (pin "40") (pinfunction "RXD_MHX_40") (pintype "bidirectional"))
    )
    (net (code "76") (name "unconnected-(H1-SENSE-Pad27)") (class "Default")
      (node (ref "H1") (pin "27") (pinfunction "SENSE_27") (pintype "bidirectional"))
    )
    (net (code "77") (name "unconnected-(H1-TXD_MHX-Pad39)") (class "Default")
      (node (ref "H1") (pin "39") (pinfunction "TXD_MHX_39") (pintype "bidirectional"))
    )
    (net (code "78") (name "unconnected-(H1-VBACKUP-Pad42)") (class "Default")
      (node (ref "H1") (pin "42") (pinfunction "VBACKUP_42") (pintype "bidirectional"))
    )
    (net (code "79") (name "unconnected-(H1-VREF0-Pad26)") (class "Default")
      (node (ref "H1") (pin "26") (pinfunction "VREF0_26") (pintype "bidirectional"))
    )
    (net (code "80") (name "unconnected-(H1-VREF1-Pad28)") (class "Default")
      (node (ref "H1") (pin "28") (pinfunction "VREF1_28") (pintype "bidirectional"))
    )
    (net (code "81") (name "unconnected-(H1-VREF2-Pad30)") (class "Default")
      (node (ref "H1") (pin "30") (pinfunction "VREF2_30") (pintype "bidirectional"))
    )
    (net (code "82") (name "unconnected-(H2-+5V_SYS-Pad25)") (class "Default")
      (node (ref "H2") (pin "25") (pinfunction "+5V_SYS_25") (pintype "bidirectional"))
    )
    (net (code "83") (name "unconnected-(H2-+5V_SYS-Pad26)") (class "Default")
      (node (ref "H2") (pin "26") (pinfunction "+5V_SYS_26") (pintype "bidirectional"))
    )
    (net (code "84") (name "unconnected-(H2-AGND-Pad31)") (class "Default")
      (node (ref "H2") (pin "31") (pinfunction "AGND_31") (pintype "bidirectional"))
    )
    (net (code "85") (name "unconnected-(H2-IO_24-Pad24)") (class "Default")
      (node (ref "H2") (pin "24") (pinfunction "IO_24_24") (pintype "bidirectional"))
    )
    (net (code "86") (name "unconnected-(H2-IO_25-Pad23)") (class "Default")
      (node (ref "H2") (pin "23") (pinfunction "IO_25_23") (pintype "bidirectional"))
    )
    (net (code "87") (name "unconnected-(H2-IO_26-Pad22)") (class "Default")
      (node (ref "H2") (pin "22") (pinfunction "IO_26_22") (pintype "bidirectional"))
    )
    (net (code "88") (name "unconnected-(H2-IO_27-Pad21)") (class "Default")
      (node (ref "H2") (pin "21") (pinfunction "IO_27_21") (pintype "bidirectional"))
    )
    (net (code "89") (name "unconnected-(H2-IO_28-Pad20)") (class "Default")
      (node (ref "H2") (pin "20") (pinfunction "IO_28_20") (pintype "bidirectional"))
    )
    (net (code "90") (name "unconnected-(H2-IO_29-Pad19)") (class "Default")
      (node (ref "H2") (pin "19") (pinfunction "IO_29_19") (pintype "bidirectional"))
    )
    (net (code "91") (name "unconnected-(H2-IO_30-Pad18)") (class "Default")
      (node (ref "H2") (pin "18") (pinfunction "IO_30_18") (pintype "bidirectional"))
    )
    (net (code "92") (name "unconnected-(H2-IO_31-Pad17)") (class "Default")
      (node (ref "H2") (pin "17") (pinfunction "IO_31_17") (pintype "bidirectional"))
    )
    (net (code "93") (name "unconnected-(H2-IO_33-Pad15)") (class "Default")
      (node (ref "H2") (pin "15") (pinfunction "IO_33_15") (pintype "bidirectional"))
    )
    (net (code "94") (name "unconnected-(H2-IO_34-Pad14)") (class "Default")
      (node (ref "H2") (pin "14") (pinfunction "IO_34_14") (pintype "bidirectional"))
    )
    (net (code "95") (name "unconnected-(H2-IO_35-Pad13)") (class "Default")
      (node (ref "H2") (pin "13") (pinfunction "IO_35_13") (pintype "bidirectional"))
    )
    (net (code "96") (name "unconnected-(H2-IO_36-Pad12)") (class "Default")
      (node (ref "H2") (pin "12") (pinfunction "IO_36_12") (pintype "bidirectional"))
    )
    (net (code "97") (name "unconnected-(H2-IO_37-Pad11)") (class "Default")
      (node (ref "H2") (pin "11") (pinfunction "IO_37_11") (pintype "bidirectional"))
    )
    (net (code "98") (name "unconnected-(H2-IO_38-Pad10)") (class "Default")
      (node (ref "H2") (pin "10") (pinfunction "IO_38_10") (pintype "bidirectional"))
    )
    (net (code "99") (name "unconnected-(H2-IO_39-Pad09)") (class "Default")
      (node (ref "H2") (pin "09") (pinfunction "IO_39_09") (pintype "bidirectional"))
    )
    (net (code "100") (name "unconnected-(H2-IO_40-Pad08)") (class "Default")
      (node (ref "H2") (pin "08") (pinfunction "IO_40_08") (pintype "bidirectional"))
    )
    (net (code "101") (name "unconnected-(H2-IO_41-Pad07)") (class "Default")
      (node (ref "H2") (pin "07") (pinfunction "IO_41_07") (pintype "bidirectional"))
    )
    (net (code "102") (name "unconnected-(H2-IO_42-Pad06)") (class "Default")
      (node (ref "H2") (pin "06") (pinfunction "IO_42_06") (pintype "bidirectional"))
    )
    (net (code "103") (name "unconnected-(H2-IO_43-Pad05)") (class "Default")
      (node (ref "H2") (pin "05") (pinfunction "IO_43_05") (pintype "bidirectional"))
    )
    (net (code "104") (name "unconnected-(H2-IO_44-Pad04)") (class "Default")
      (node (ref "H2") (pin "04") (pinfunction "IO_44_04") (pintype "bidirectional"))
    )
    (net (code "105") (name "unconnected-(H2-IO_45-Pad03)") (class "Default")
      (node (ref "H2") (pin "03") (pinfunction "IO_45_03") (pintype "bidirectional"))
    )
    (net (code "106") (name "unconnected-(H2-IO_46-Pad02)") (class "Default")
      (node (ref "H2") (pin "02") (pinfunction "IO_46_02") (pintype "bidirectional"))
    )
    (net (code "107") (name "unconnected-(H2-IO_47-Pad01)") (class "Default")
      (node (ref "H2") (pin "01") (pinfunction "IO_47_01") (pintype "bidirectional"))
    )
    (net (code "108") (name "unconnected-(H2-S0-Pad33)") (class "Default")
      (node (ref "H2") (pin "33") (pinfunction "S0_33") (pintype "bidirectional"))
    )
    (net (code "109") (name "unconnected-(H2-S0-Pad34)") (class "Default")
      (node (ref "H2") (pin "34") (pinfunction "S0_34") (pintype "bidirectional"))
    )
    (net (code "110") (name "unconnected-(H2-S1-Pad35)") (class "Default")
      (node (ref "H2") (pin "35") (pinfunction "S1_35") (pintype "bidirectional"))
    )
    (net (code "111") (name "unconnected-(H2-S1-Pad36)") (class "Default")
      (node (ref "H2") (pin "36") (pinfunction "S1_36") (pintype "bidirectional"))
    )
    (net (code "112") (name "unconnected-(H2-S2-Pad37)") (class "Default")
      (node (ref "H2") (pin "37") (pinfunction "S2_37") (pintype "bidirectional"))
    )
    (net (code "113") (name "unconnected-(H2-S2-Pad38)") (class "Default")
      (node (ref "H2") (pin "38") (pinfunction "S2_38") (pintype "bidirectional"))
    )
    (net (code "114") (name "unconnected-(H2-S3-Pad39)") (class "Default")
      (node (ref "H2") (pin "39") (pinfunction "S3_39") (pintype "bidirectional"))
    )
    (net (code "115") (name "unconnected-(H2-S3-Pad40)") (class "Default")
      (node (ref "H2") (pin "40") (pinfunction "S3_40") (pintype "bidirectional"))
    )
    (net (code "116") (name "unconnected-(H2-S4-Pad41)") (class "Default")
      (node (ref "H2") (pin "41") (pinfunction "S4_41") (pintype "bidirectional"))
    )
    (net (code "117") (name "unconnected-(H2-S4-Pad42)") (class "Default")
      (node (ref "H2") (pin "42") (pinfunction "S4_42") (pintype "bidirectional"))
    )
    (net (code "118") (name "unconnected-(H2-S5-Pad43)") (class "Default")
      (node (ref "H2") (pin "43") (pinfunction "S5_43") (pintype "bidirectional"))
    )
    (net (code "119") (name "unconnected-(H2-S5-Pad44)") (class "Default")
      (node (ref "H2") (pin "44") (pinfunction "S5_44") (pintype "bidirectional"))
    )
    (net (code "120") (name "unconnected-(H2-VBATT-Pad45)") (class "Default")
      (node (ref "H2") (pin "45") (pinfunction "VBATT_45") (pintype "bidirectional"))
    )
    (net (code "121") (name "unconnected-(H2-VBATT-Pad46)") (class "Default")
      (node (ref "H2") (pin "46") (pinfunction "VBATT_46") (pintype "bidirectional"))
    )
    (net (code "122") (name "unconnected-(J8-Pad1)") (class "Default")
      (node (ref "J8") (pin "1") (pinfunction "1_1") (pintype "passive"))
    )
    (net (code "123") (name "unconnected-(J8-Pad12)") (class "Default")
      (node (ref "J8") (pin "12") (pinfunction "12_12") (pintype "passive"))
    )
    (net (code "124") (name "unconnected-(J8-Pad13)") (class "Default")
      (node (ref "J8") (pin "13") (pinfunction "13_13") (pintype "passive"))
    )
    (net (code "125") (name "unconnected-(J8-Pad19)") (class "Default")
      (node (ref "J8") (pin "19") (pinfunction "19_19") (pintype "passive"))
    )
    (net (code "126") (name "unconnected-(J8-Pad20)") (class "Default")
      (node (ref "J8") (pin "20") (pinfunction "20_20") (pintype "passive"))
    )
    (net (code "127") (name "unconnected-(J8-Pad23)") (class "Default")
      (node (ref "J8") (pin "23") (pinfunction "23_23") (pintype "passive"))
    )
    (net (code "128") (name "unconnected-(J8-Pad24)") (class "Default")
      (node (ref "J8") (pin "24") (pinfunction "24_24") (pintype "passive"))
    )
    (net (code "129") (name "unconnected-(J8-Pad25)") (class "Default")
      (node (ref "J8") (pin "25") (pinfunction "25_25") (pintype "passive"))
    )
    (net (code "130") (name "unconnected-(J8-Pad26)") (class "Default")
      (node (ref "J8") (pin "26") (pinfunction "26_26") (pintype "passive"))
    )
    (net (code "131") (name "unconnected-(J8-Pad27)") (class "Default")
      (node (ref "J8") (pin "27") (pinfunction "27_27") (pintype "passive"))
    )
    (net (code "132") (name "unconnected-(MT1-P$1-Pad1)") (class "Default")
      (node (ref "MT1") (pin "1") (pinfunction "P$1_1") (pintype "bidirectional"))
    )
    (net (code "133") (name "unconnected-(MT2-P$1-Pad1)") (class "Default")
      (node (ref "MT2") (pin "1") (pinfunction "P$1_1") (pintype "bidirectional"))
    )
    (net (code "134") (name "unconnected-(MT3-P$1-Pad1)") (class "Default")
      (node (ref "MT3") (pin "1") (pinfunction "P$1_1") (pintype "bidirectional"))
    )
    (net (code "135") (name "unconnected-(MT4-P$1-Pad1)") (class "Default")
      (node (ref "MT4") (pin "1") (pinfunction "P$1_1") (pintype "bidirectional"))
    )
    (net (code "136") (name "unconnected-(U1-NC{slash}ADJ-Pad4)") (class "Default")
      (node (ref "U1") (pin "4") (pinfunction "NC/ADJ_4") (pintype "bidirectional"))
    )
    (net (code "137") (name "unconnected-(U2-NC{slash}ADJ-Pad4)") (class "Default")
      (node (ref "U2") (pin "4") (pinfunction "NC/ADJ_4") (pintype "bidirectional"))
    )
    (net (code "138") (name "unconnected-(U4-NC{slash}ADJ-Pad4)") (class "Default")
      (node (ref "U4") (pin "4") (pinfunction "NC/ADJ_4") (pintype "bidirectional"))
    )
    (net (code "139") (name "unconnected-(Y1-NC-Pad1)") (class "Default")
      (node (ref "Y1") (pin "1") (pinfunction "NC_1") (pintype "no_connect"))
    )
  )
)
